# INPUT.net
KiCad netlist of a schematic drawn in Altium Designer
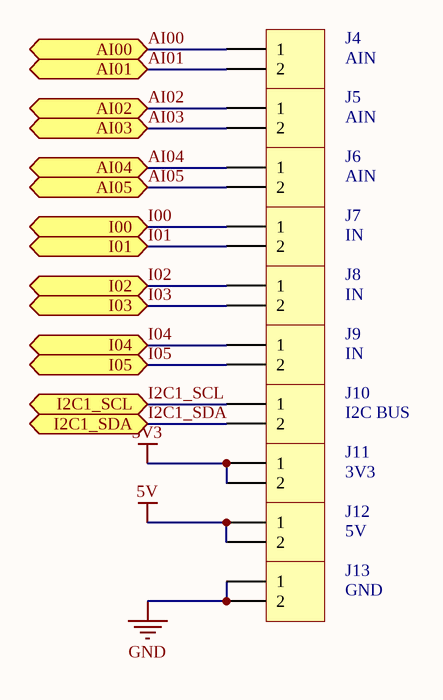
[diagram p0: INPUT.SchDoc]

(export (version "E")
  (design (tool "Eeschema 10.0.6"))
  (components
    (comp (ref "J4")
      (value "AIN")
      (footprint "DOMINO NORMAL 2")
      (description "Header, 2-Pin")
      (fields (field (name "PUBLISHER") "Altium Limited"))
      (libsource (lib "RobotClub") (part "Header 2"))
    )
    (comp (ref "J5")
      (value "AIN")
      (footprint "DOMINO NORMAL 2")
      (description "Header, 2-Pin")
      (fields (field (name "PUBLISHER") "Altium Limited"))
      (libsource (lib "RobotClub") (part "Header 2"))
    )
    (comp (ref "J6")
      (value "AIN")
      (footprint "DOMINO NORMAL 2")
      (description "Header, 2-Pin")
      (fields (field (name "PUBLISHER") "Altium Limited"))
      (libsource (lib "RobotClub") (part "Header 2"))
    )
    (comp (ref "J7")
      (value "IN")
      (footprint "DOMINO NORMAL 2")
      (description "Header, 2-Pin")
      (fields (field (name "PUBLISHER") "Altium Limited"))
      (libsource (lib "RobotClub") (part "Header 2"))
    )
    (comp (ref "J8")
      (value "IN")
      (footprint "DOMINO NORMAL 2")
      (description "Header, 2-Pin")
      (fields (field (name "PUBLISHER") "Altium Limited"))
      (libsource (lib "RobotClub") (part "Header 2"))
    )
    (comp (ref "J9")
      (value "IN")
      (footprint "DOMINO NORMAL 2")
      (description "Header, 2-Pin")
      (fields (field (name "PUBLISHER") "Altium Limited"))
      (libsource (lib "RobotClub") (part "Header 2"))
    )
    (comp (ref "J10")
      (value "I2C BUS")
      (footprint "DOMINO NORMAL 2")
      (description "Header, 2-Pin")
      (fields (field (name "PUBLISHER") "Altium Limited"))
      (libsource (lib "RobotClub") (part "Header 2"))
    )
    (comp (ref "J11")
      (value "3V3")
      (footprint "DOMINO NORMAL 2")
      (description "Header, 2-Pin")
      (fields (field (name "PUBLISHER") "Altium Limited"))
      (libsource (lib "RobotClub") (part "Header 2"))
    )
    (comp (ref "J12")
      (value "5V")
      (footprint "DOMINO NORMAL 2")
      (description "Header, 2-Pin")
      (fields (field (name "PUBLISHER") "Altium Limited"))
      (libsource (lib "RobotClub") (part "Header 2"))
    )
    (comp (ref "J13")
      (value "GND")
      (footprint "DOMINO NORMAL 2")
      (description "Header, 2-Pin")
      (fields (field (name "PUBLISHER") "Altium Limited"))
      (libsource (lib "RobotClub") (part "Header 2"))
    )
  )
  (nets
    (net (code "1") (name "/AI00") (class "Default")
      (node (ref "J4") (pin "1") (pinfunction "1_1") (pintype "passive"))
    )
    (net (code "2") (name "/AI01") (class "Default")
      (node (ref "J4") (pin "2") (pinfunction "2_2") (pintype "passive"))
    )
    (net (code "3") (name "/AI02") (class "Default")
      (node (ref "J5") (pin "1") (pinfunction "1_1") (pintype "passive"))
    )
    (net (code "4") (name "/AI03") (class "Default")
      (node (ref "J5") (pin "2") (pinfunction "2_2") (pintype "passive"))
    )
    (net (code "5") (name "/AI04") (class "Default")
      (node (ref "J6") (pin "1") (pinfunction "1_1") (pintype "passive"))
    )
    (net (code "6") (name "/AI05") (class "Default")
      (node (ref "J6") (pin "2") (pinfunction "2_2") (pintype "passive"))
    )
    (net (code "7") (name "/I00") (class "Default")
      (node (ref "J7") (pin "1") (pinfunction "1_1") (pintype "passive"))
    )
    (net (code "8") (name "/I01") (class "Default")
      (node (ref "J7") (pin "2") (pinfunction "2_2") (pintype "passive"))
    )
    (net (code "9") (name "/I02") (class "Default")
      (node (ref "J8") (pin "1") (pinfunction "1_1") (pintype "passive"))
    )
    (net (code "10") (name "/I2C1_SCL") (class "Default")
      (node (ref "J10") (pin "1") (pinfunction "1_1") (pintype "passive"))
    )
    (net (code "11") (name "/I2C1_SDA") (class "Default")
      (node (ref "J10") (pin "2") (pinfunction "2_2") (pintype "passive"))
    )
    (net (code "12") (name "/I03") (class "Default")
      (node (ref "J8") (pin "2") (pinfunction "2_2") (pintype "passive"))
    )
    (net (code "13") (name "/I04") (class "Default")
      (node (ref "J9") (pin "1") (pinfunction "1_1") (pintype "passive"))
    )
    (net (code "14") (name "/I05") (class "Default")
      (node (ref "J9") (pin "2") (pinfunction "2_2") (pintype "passive"))
    )
    (net (code "15") (name "3V3") (class "Default")
      (node (ref "J11") (pin "1") (pinfunction "1_1") (pintype "passive"))
      (node (ref "J11") (pin "2") (pinfunction "2_2") (pintype "passive"))
    )
    (net (code "16") (name "5V") (class "Default")
      (node (ref "J12") (pin "1") (pinfunction "1_1") (pintype "passive"))
      (node (ref "J12") (pin "2") (pinfunction "2_2") (pintype "passive"))
    )
    (net (code "17") (name "GND") (class "Default")
      (node (ref "J13") (pin "1") (pinfunction "1_1") (pintype "passive"))
      (node (ref "J13") (pin "2") (pinfunction "2_2") (pintype "passive"))
    )
  )
)
